# headphone-amp.net
KiCad netlist of a schematic drawn in EAGLE
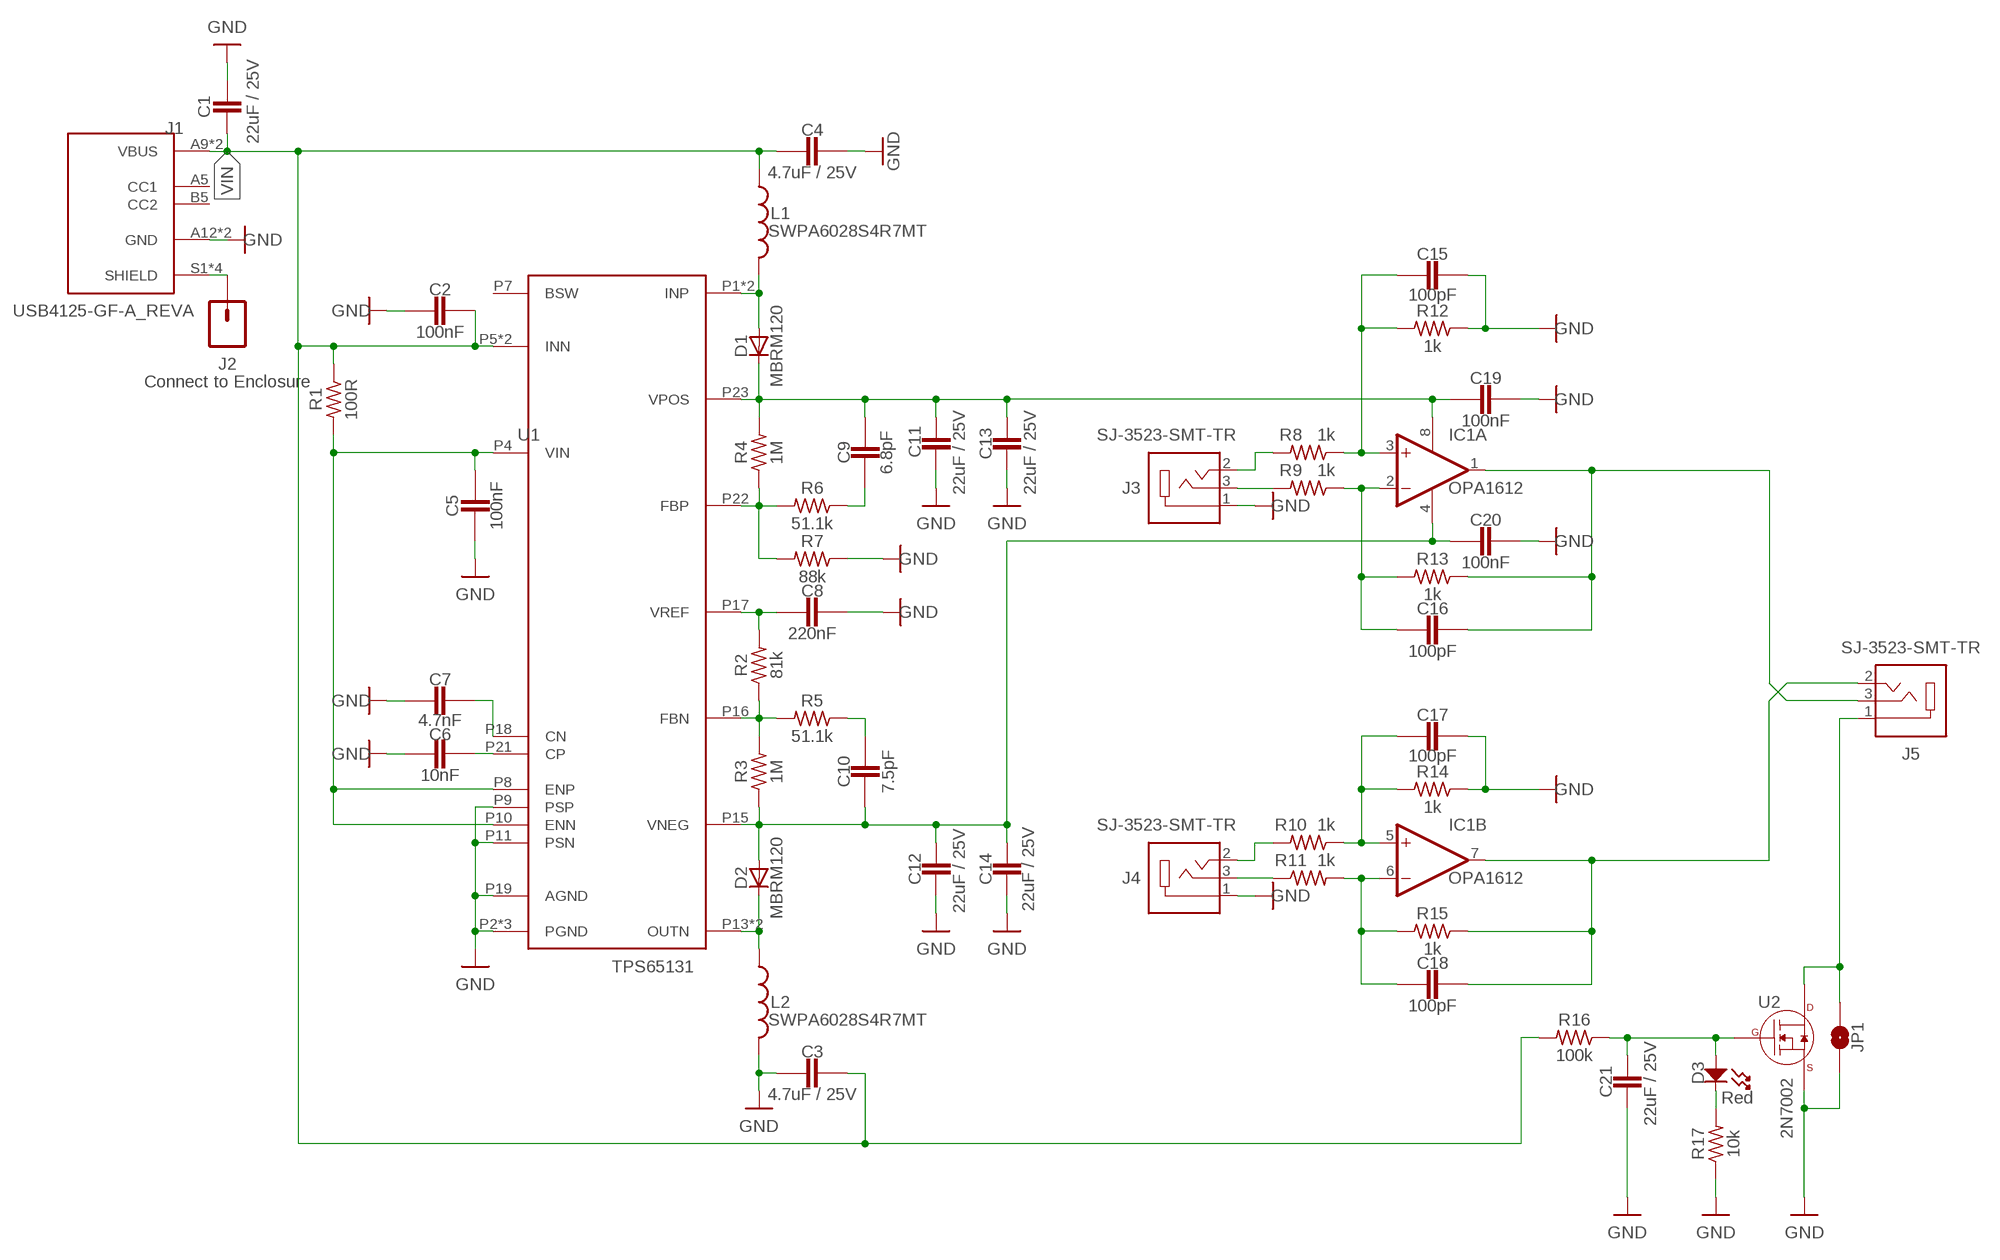
[diagram p0: schematic, sheet 1]

(export (version "E")
  (design (tool "Eeschema 10.0.6"))
  (components
    (comp (ref "C1")
      (value "22uF / 25V")
      (footprint "eagle-import:C0805")
      (libsource (lib "eagle-import") (part "C-EUC0805"))
    )
    (comp (ref "C2")
      (value "100nF")
      (footprint "eagle-import:C0402")
      (libsource (lib "eagle-import") (part "CAPACITOR-0402"))
    )
    (comp (ref "C3")
      (value "4.7uF / 25V")
      (footprint "eagle-import:C0402")
      (libsource (lib "eagle-import") (part "CAPACITOR-0402"))
    )
    (comp (ref "C4")
      (value "4.7uF / 25V")
      (footprint "eagle-import:C0402")
      (libsource (lib "eagle-import") (part "CAPACITOR-0402"))
    )
    (comp (ref "C5")
      (value "100nF")
      (footprint "eagle-import:C0402")
      (libsource (lib "eagle-import") (part "CAPACITOR-0402"))
    )
    (comp (ref "C6")
      (value "10nF")
      (footprint "eagle-import:C0402")
      (libsource (lib "eagle-import") (part "CAPACITOR-0402"))
    )
    (comp (ref "C7")
      (value "4.7nF")
      (footprint "eagle-import:C0402")
      (libsource (lib "eagle-import") (part "CAPACITOR-0402"))
    )
    (comp (ref "C8")
      (value "220nF")
      (footprint "eagle-import:C0402")
      (libsource (lib "eagle-import") (part "CAPACITOR-0402"))
    )
    (comp (ref "C9")
      (value "6.8pF")
      (footprint "eagle-import:C0402")
      (libsource (lib "eagle-import") (part "CAPACITOR-0402"))
    )
    (comp (ref "C10")
      (value "7.5pF")
      (footprint "eagle-import:C0402")
      (libsource (lib "eagle-import") (part "CAPACITOR-0402"))
    )
    (comp (ref "C11")
      (value "22uF / 25V")
      (footprint "eagle-import:C0805")
      (libsource (lib "eagle-import") (part "C-EUC0805"))
    )
    (comp (ref "C12")
      (value "22uF / 25V")
      (footprint "eagle-import:C0805")
      (libsource (lib "eagle-import") (part "C-EUC0805"))
    )
    (comp (ref "C13")
      (value "22uF / 25V")
      (footprint "eagle-import:C0805")
      (libsource (lib "eagle-import") (part "C-EUC0805"))
    )
    (comp (ref "C14")
      (value "22uF / 25V")
      (footprint "eagle-import:C0805")
      (libsource (lib "eagle-import") (part "C-EUC0805"))
    )
    (comp (ref "C15")
      (value "100pF")
      (footprint "eagle-import:C0402")
      (libsource (lib "eagle-import") (part "CAPACITOR-0402"))
    )
    (comp (ref "C16")
      (value "100pF")
      (footprint "eagle-import:C0402")
      (libsource (lib "eagle-import") (part "CAPACITOR-0402"))
    )
    (comp (ref "C17")
      (value "100pF")
      (footprint "eagle-import:C0402")
      (libsource (lib "eagle-import") (part "CAPACITOR-0402"))
    )
    (comp (ref "C18")
      (value "100pF")
      (footprint "eagle-import:C0402")
      (libsource (lib "eagle-import") (part "CAPACITOR-0402"))
    )
    (comp (ref "C19")
      (value "100nF")
      (footprint "eagle-import:C0402")
      (libsource (lib "eagle-import") (part "CAPACITOR-0402"))
    )
    (comp (ref "C20")
      (value "100nF")
      (footprint "eagle-import:C0402")
      (libsource (lib "eagle-import") (part "CAPACITOR-0402"))
    )
    (comp (ref "C21")
      (value "22uF / 25V")
      (footprint "eagle-import:C0805")
      (libsource (lib "eagle-import") (part "C-EUC0805"))
    )
    (comp (ref "D1")
      (value "MBRM120")
      (footprint "eagle-import:POWERMITE")
      (libsource (lib "eagle-import") (part "MBRM120"))
    )
    (comp (ref "D2")
      (value "MBRM120")
      (footprint "eagle-import:POWERMITE")
      (libsource (lib "eagle-import") (part "MBRM120"))
    )
    (comp (ref "D3")
      (value "Red")
      (footprint "eagle-import:LED0603")
      (fields (field (name "HOUSEPART") "NO"))
      (libsource (lib "eagle-import") (part "LED_SINGLE-0603"))
    )
    (comp (ref "IC1")
      (value "OPA1612")
      (footprint "eagle-import:SO08")
      (libsource (lib "eagle-import") (part "OPA2UA134"))
    )
    (comp (ref "J1")
      (value "USB4125-GF-A_REVA")
      (footprint "eagle-import:GCT_USB4125-GF-A_REVA")
      (fields (field (name "MF") "Global Connector Technology") (field (name "MP") "USB4125-GF-A"))
      (libsource (lib "eagle-import") (part "USB4125-GF-A_REVA"))
    )
    (comp (ref "J2")
      (value "CONN_01")
      (footprint "eagle-import:1X01")
      (libsource (lib "eagle-import") (part "CONN_01"))
    )
    (comp (ref "J3")
      (value "SJ-3523-SMT-TR")
      (footprint "eagle-import:CUI_SJ-3523-SMT-TR")
      (fields (field (name "MF") "CUI Devices"))
      (libsource (lib "eagle-import") (part "SJ-3523-SMT-TR"))
    )
    (comp (ref "J4")
      (value "SJ-3523-SMT-TR")
      (footprint "eagle-import:CUI_SJ-3523-SMT-TR")
      (fields (field (name "MF") "CUI Devices"))
      (libsource (lib "eagle-import") (part "SJ-3523-SMT-TR"))
    )
    (comp (ref "J5")
      (value "SJ-3523-SMT-TR")
      (footprint "eagle-import:CUI_SJ-3523-SMT-TR")
      (fields (field (name "MF") "CUI Devices"))
      (libsource (lib "eagle-import") (part "SJ-3523-SMT-TR"))
    )
    (comp (ref "JP1")
      (value "JUMPER-SMT_2_NO_SILK")
      (footprint "eagle-import:SMT-JUMPER_2_NO_SILK")
      (libsource (lib "eagle-import") (part "JUMPER-SMT_2_NO_SILK"))
    )
    (comp (ref "L1")
      (value "SWPA6028S4R7MT")
      (footprint "eagle-import:POWER-CHOKE_WE-TPC")
      (libsource (lib "eagle-import") (part "L-USWE-TPC"))
    )
    (comp (ref "L2")
      (value "SWPA6028S4R7MT")
      (footprint "eagle-import:POWER-CHOKE_WE-TPC")
      (libsource (lib "eagle-import") (part "L-USWE-TPC"))
    )
    (comp (ref "R1")
      (value "100R")
      (footprint "eagle-import:R0402")
      (libsource (lib "eagle-import") (part "R-US_R0402"))
    )
    (comp (ref "R2")
      (value "81k")
      (footprint "eagle-import:R0402")
      (libsource (lib "eagle-import") (part "R-US_R0402"))
    )
    (comp (ref "R3")
      (value "1M")
      (footprint "eagle-import:R0402")
      (libsource (lib "eagle-import") (part "R-US_R0402"))
    )
    (comp (ref "R4")
      (value "1M")
      (footprint "eagle-import:R0402")
      (libsource (lib "eagle-import") (part "R-US_R0402"))
    )
    (comp (ref "R5")
      (value "51.1k")
      (footprint "eagle-import:R0402")
      (libsource (lib "eagle-import") (part "R-US_R0402"))
    )
    (comp (ref "R6")
      (value "51.1k")
      (footprint "eagle-import:R0402")
      (libsource (lib "eagle-import") (part "R-US_R0402"))
    )
    (comp (ref "R7")
      (value "88k")
      (footprint "eagle-import:R0402")
      (libsource (lib "eagle-import") (part "R-US_R0402"))
    )
    (comp (ref "R8")
      (value "1k")
      (footprint "eagle-import:R0402")
      (libsource (lib "eagle-import") (part "R-US_R0402"))
    )
    (comp (ref "R9")
      (value "1k")
      (footprint "eagle-import:R0402")
      (libsource (lib "eagle-import") (part "R-US_R0402"))
    )
    (comp (ref "R10")
      (value "1k")
      (footprint "eagle-import:R0402")
      (libsource (lib "eagle-import") (part "R-US_R0402"))
    )
    (comp (ref "R11")
      (value "1k")
      (footprint "eagle-import:R0402")
      (libsource (lib "eagle-import") (part "R-US_R0402"))
    )
    (comp (ref "R12")
      (value "1k")
      (footprint "eagle-import:R0402")
      (libsource (lib "eagle-import") (part "R-US_R0402"))
    )
    (comp (ref "R13")
      (value "1k")
      (footprint "eagle-import:R0402")
      (libsource (lib "eagle-import") (part "R-US_R0402"))
    )
    (comp (ref "R14")
      (value "1k")
      (footprint "eagle-import:R0402")
      (libsource (lib "eagle-import") (part "R-US_R0402"))
    )
    (comp (ref "R15")
      (value "1k")
      (footprint "eagle-import:R0402")
      (libsource (lib "eagle-import") (part "R-US_R0402"))
    )
    (comp (ref "R16")
      (value "100k")
      (footprint "eagle-import:R0402")
      (libsource (lib "eagle-import") (part "R-US_R0402"))
    )
    (comp (ref "R17")
      (value "10k")
      (footprint "eagle-import:R0402")
      (libsource (lib "eagle-import") (part "R-US_R0402"))
    )
    (comp (ref "U1")
      (value "TPS65131")
      (footprint "eagle-import:QFN24-4X4-2")
      (libsource (lib "eagle-import") (part "TPS65131"))
    )
    (comp (ref "U2")
      (value "2N7002")
      (footprint "eagle-import:SOT-23-3")
      (fields (field (name "HOUSEPART") "NO"))
      (libsource (lib "eagle-import") (part "N-CHANNEL_FET_SOT-23-3"))
    )
  )
  (nets
    (net (code "1") (name "GND") (class "Default")
      (node (ref "C1") (pin "1") (pinfunction "1_1") (pintype "passive"))
      (node (ref "C11") (pin "2") (pinfunction "2_2") (pintype "passive"))
      (node (ref "C12") (pin "2") (pinfunction "2_2") (pintype "passive"))
      (node (ref "C13") (pin "2") (pinfunction "2_2") (pintype "passive"))
      (node (ref "C14") (pin "2") (pinfunction "2_2") (pintype "passive"))
      (node (ref "C15") (pin "1") (pinfunction "1_1") (pintype "passive"))
      (node (ref "C17") (pin "1") (pinfunction "1_1") (pintype "passive"))
      (node (ref "C19") (pin "2") (pinfunction "2_2") (pintype "passive"))
      (node (ref "C2") (pin "1") (pinfunction "1_1") (pintype "passive"))
      (node (ref "C20") (pin "2") (pinfunction "2_2") (pintype "passive"))
      (node (ref "C21") (pin "2") (pinfunction "2_2") (pintype "passive"))
      (node (ref "C3") (pin "2") (pinfunction "2_2") (pintype "passive"))
      (node (ref "C4") (pin "1") (pinfunction "1_1") (pintype "passive"))
      (node (ref "C5") (pin "2") (pinfunction "2_2") (pintype "passive"))
      (node (ref "C6") (pin "2") (pinfunction "2_2") (pintype "passive"))
      (node (ref "C7") (pin "2") (pinfunction "2_2") (pintype "passive"))
      (node (ref "C8") (pin "1") (pinfunction "1_1") (pintype "passive"))
      (node (ref "J1") (pin "A12") (pinfunction "GND_A12") (pintype "power_in"))
      (node (ref "J1") (pin "B12") (pinfunction "GND_B12") (pintype "power_in"))
      (node (ref "J3") (pin "1") (pinfunction "1_1") (pintype "passive"))
      (node (ref "J4") (pin "1") (pinfunction "1_1") (pintype "passive"))
      (node (ref "JP1") (pin "1") (pinfunction "1_1") (pintype "passive"))
      (node (ref "L2") (pin "2") (pinfunction "2_2") (pintype "passive"))
      (node (ref "R12") (pin "1") (pinfunction "1_1") (pintype "passive"))
      (node (ref "R14") (pin "1") (pinfunction "1_1") (pintype "passive"))
      (node (ref "R17") (pin "1") (pinfunction "1_1") (pintype "passive"))
      (node (ref "R7") (pin "1") (pinfunction "1_1") (pintype "passive"))
      (node (ref "U1") (pin "P11") (pinfunction "PSN_P11") (pintype "bidirectional"))
      (node (ref "U1") (pin "P19") (pinfunction "AGND_P19") (pintype "bidirectional"))
      (node (ref "U1") (pin "P2") (pinfunction "PGND_P2") (pintype "bidirectional"))
      (node (ref "U1") (pin "P3") (pinfunction "PGND_P3") (pintype "bidirectional"))
      (node (ref "U1") (pin "P9") (pinfunction "PSP_P9") (pintype "bidirectional"))
      (node (ref "U1") (pin "PAD") (pinfunction "PGND_PAD") (pintype "bidirectional"))
      (node (ref "U2") (pin "P$2") (pinfunction "SOURCE_P$2") (pintype "bidirectional"))
    )
    (net (code "2") (name "Net-(C9-Pad2)") (class "Default")
      (node (ref "C9") (pin "2") (pinfunction "2_2") (pintype "passive"))
      (node (ref "R6") (pin "1") (pinfunction "1_1") (pintype "passive"))
    )
    (net (code "3") (name "Net-(C10-Pad2)") (class "Default")
      (node (ref "C10") (pin "2") (pinfunction "2_2") (pintype "passive"))
      (node (ref "R5") (pin "1") (pinfunction "1_1") (pintype "passive"))
    )
    (net (code "4") (name "Net-(D1-A)") (class "Default")
      (node (ref "D1") (pin "P$2") (pinfunction "A_P$2") (pintype "passive"))
      (node (ref "L1") (pin "2") (pinfunction "2_2") (pintype "passive"))
      (node (ref "U1") (pin "P1") (pinfunction "INP_P1") (pintype "bidirectional"))
      (node (ref "U1") (pin "P24") (pinfunction "INP_P24") (pintype "bidirectional"))
    )
    (net (code "5") (name "Net-(D1-C)") (class "Default")
      (node (ref "C11") (pin "1") (pinfunction "1_1") (pintype "passive"))
      (node (ref "C13") (pin "1") (pinfunction "1_1") (pintype "passive"))
      (node (ref "C19") (pin "1") (pinfunction "1_1") (pintype "passive"))
      (node (ref "C9") (pin "1") (pinfunction "1_1") (pintype "passive"))
      (node (ref "D1") (pin "P$1") (pinfunction "C_P$1") (pintype "passive"))
      (node (ref "IC1") (pin "8") (pinfunction "V+_8") (pintype "power_in"))
      (node (ref "R4") (pin "2") (pinfunction "2_2") (pintype "passive"))
      (node (ref "U1") (pin "P23") (pinfunction "VPOS_P23") (pintype "bidirectional"))
    )
    (net (code "6") (name "Net-(D2-A)") (class "Default")
      (node (ref "C10") (pin "1") (pinfunction "1_1") (pintype "passive"))
      (node (ref "C12") (pin "1") (pinfunction "1_1") (pintype "passive"))
      (node (ref "C14") (pin "1") (pinfunction "1_1") (pintype "passive"))
      (node (ref "C20") (pin "1") (pinfunction "1_1") (pintype "passive"))
      (node (ref "D2") (pin "P$2") (pinfunction "A_P$2") (pintype "passive"))
      (node (ref "IC1") (pin "4") (pinfunction "V-_4") (pintype "power_in"))
      (node (ref "R3") (pin "1") (pinfunction "1_1") (pintype "passive"))
      (node (ref "U1") (pin "P15") (pinfunction "VNEG_P15") (pintype "bidirectional"))
    )
    (net (code "7") (name "Net-(D2-C)") (class "Default")
      (node (ref "D2") (pin "P$1") (pinfunction "C_P$1") (pintype "passive"))
      (node (ref "L2") (pin "1") (pinfunction "1_1") (pintype "passive"))
      (node (ref "U1") (pin "P13") (pinfunction "OUTN_P13") (pintype "bidirectional"))
      (node (ref "U1") (pin "P14") (pinfunction "OUTN_P14") (pintype "bidirectional"))
    )
    (net (code "8") (name "Net-(D3-PadCATHODE)") (class "Default")
      (node (ref "D3") (pin "CATHODE") (pinfunction "CATHODE_CATHODE") (pintype "power_in"))
      (node (ref "R17") (pin "2") (pinfunction "2_2") (pintype "passive"))
    )
    (net (code "9") (name "Net-(IC1A-+IN)") (class "Default")
      (node (ref "C15") (pin "2") (pinfunction "2_2") (pintype "passive"))
      (node (ref "IC1") (pin "3") (pinfunction "+IN_3") (pintype "input"))
      (node (ref "R12") (pin "2") (pinfunction "2_2") (pintype "passive"))
      (node (ref "R8") (pin "1") (pinfunction "1_1") (pintype "passive"))
    )
    (net (code "10") (name "Net-(IC1A--IN)") (class "Default")
      (node (ref "C16") (pin "2") (pinfunction "2_2") (pintype "passive"))
      (node (ref "IC1") (pin "2") (pinfunction "-IN_2") (pintype "input"))
      (node (ref "R13") (pin "2") (pinfunction "2_2") (pintype "passive"))
      (node (ref "R9") (pin "1") (pinfunction "1_1") (pintype "passive"))
    )
    (net (code "11") (name "Net-(IC1A-OUT)") (class "Default")
      (node (ref "C16") (pin "1") (pinfunction "1_1") (pintype "passive"))
      (node (ref "IC1") (pin "1") (pinfunction "OUT_1") (pintype "output"))
      (node (ref "J5") (pin "3") (pinfunction "3_3") (pintype "passive"))
      (node (ref "R13") (pin "1") (pinfunction "1_1") (pintype "passive"))
    )
    (net (code "12") (name "Net-(IC1B-+IN)") (class "Default")
      (node (ref "C17") (pin "2") (pinfunction "2_2") (pintype "passive"))
      (node (ref "IC1") (pin "5") (pinfunction "+IN_5") (pintype "input"))
      (node (ref "R10") (pin "1") (pinfunction "1_1") (pintype "passive"))
      (node (ref "R14") (pin "2") (pinfunction "2_2") (pintype "passive"))
    )
    (net (code "13") (name "Net-(IC1B--IN)") (class "Default")
      (node (ref "C18") (pin "2") (pinfunction "2_2") (pintype "passive"))
      (node (ref "IC1") (pin "6") (pinfunction "-IN_6") (pintype "input"))
      (node (ref "R11") (pin "2") (pinfunction "2_2") (pintype "passive"))
      (node (ref "R15") (pin "2") (pinfunction "2_2") (pintype "passive"))
    )
    (net (code "14") (name "Net-(IC1B-OUT)") (class "Default")
      (node (ref "C18") (pin "1") (pinfunction "1_1") (pintype "passive"))
      (node (ref "IC1") (pin "7") (pinfunction "OUT_7") (pintype "output"))
      (node (ref "J5") (pin "2") (pinfunction "2_2") (pintype "passive"))
      (node (ref "R15") (pin "1") (pinfunction "1_1") (pintype "passive"))
    )
    (net (code "15") (name "Net-(J1-SHIELD-PadS1)") (class "Default")
      (node (ref "J1") (pin "S1") (pinfunction "SHIELD_S1") (pintype "passive"))
      (node (ref "J1") (pin "S2") (pinfunction "SHIELD_S2") (pintype "passive"))
      (node (ref "J1") (pin "S3") (pinfunction "SHIELD_S3") (pintype "passive"))
      (node (ref "J1") (pin "S4") (pinfunction "SHIELD_S4") (pintype "passive"))
      (node (ref "J2") (pin "1") (pinfunction "1_1") (pintype "passive"))
    )
    (net (code "16") (name "Net-(J3-Pad2)") (class "Default")
      (node (ref "J3") (pin "2") (pinfunction "2_2") (pintype "passive"))
      (node (ref "R8") (pin "2") (pinfunction "2_2") (pintype "passive"))
    )
    (net (code "17") (name "Net-(J3-Pad3)") (class "Default")
      (node (ref "J3") (pin "3") (pinfunction "3_3") (pintype "passive"))
      (node (ref "R9") (pin "2") (pinfunction "2_2") (pintype "passive"))
    )
    (net (code "18") (name "Net-(J4-Pad2)") (class "Default")
      (node (ref "J4") (pin "2") (pinfunction "2_2") (pintype "passive"))
      (node (ref "R10") (pin "2") (pinfunction "2_2") (pintype "passive"))
    )
    (net (code "19") (name "Net-(J4-Pad3)") (class "Default")
      (node (ref "J4") (pin "3") (pinfunction "3_3") (pintype "passive"))
      (node (ref "R11") (pin "1") (pinfunction "1_1") (pintype "passive"))
    )
    (net (code "20") (name "Net-(U1-CN)") (class "Default")
      (node (ref "C7") (pin "1") (pinfunction "1_1") (pintype "passive"))
      (node (ref "U1") (pin "P18") (pinfunction "CN_P18") (pintype "bidirectional"))
    )
    (net (code "21") (name "Net-(U1-CP)") (class "Default")
      (node (ref "C6") (pin "1") (pinfunction "1_1") (pintype "passive"))
      (node (ref "U1") (pin "P21") (pinfunction "CP_P21") (pintype "bidirectional"))
    )
    (net (code "22") (name "Net-(U1-ENN)") (class "Default")
      (node (ref "C5") (pin "1") (pinfunction "1_1") (pintype "passive"))
      (node (ref "R1") (pin "2") (pinfunction "2_2") (pintype "passive"))
      (node (ref "U1") (pin "P10") (pinfunction "ENN_P10") (pintype "bidirectional"))
      (node (ref "U1") (pin "P4") (pinfunction "VIN_P4") (pintype "bidirectional"))
      (node (ref "U1") (pin "P8") (pinfunction "ENP_P8") (pintype "bidirectional"))
    )
    (net (code "23") (name "Net-(U1-FBN)") (class "Default")
      (node (ref "R2") (pin "1") (pinfunction "1_1") (pintype "passive"))
      (node (ref "R3") (pin "2") (pinfunction "2_2") (pintype "passive"))
      (node (ref "R5") (pin "2") (pinfunction "2_2") (pintype "passive"))
      (node (ref "U1") (pin "P16") (pinfunction "FBN_P16") (pintype "bidirectional"))
    )
    (net (code "24") (name "Net-(U1-FBP)") (class "Default")
      (node (ref "R4") (pin "1") (pinfunction "1_1") (pintype "passive"))
      (node (ref "R6") (pin "2") (pinfunction "2_2") (pintype "passive"))
      (node (ref "R7") (pin "2") (pinfunction "2_2") (pintype "passive"))
      (node (ref "U1") (pin "P22") (pinfunction "FBP_P22") (pintype "bidirectional"))
    )
    (net (code "25") (name "Net-(U1-VREF)") (class "Default")
      (node (ref "C8") (pin "2") (pinfunction "2_2") (pintype "passive"))
      (node (ref "R2") (pin "2") (pinfunction "2_2") (pintype "passive"))
      (node (ref "U1") (pin "P17") (pinfunction "VREF_P17") (pintype "bidirectional"))
    )
    (net (code "26") (name "Net-(U2-DRAIN)") (class "Default")
      (node (ref "J5") (pin "1") (pinfunction "1_1") (pintype "passive"))
      (node (ref "JP1") (pin "2") (pinfunction "2_2") (pintype "passive"))
      (node (ref "U2") (pin "P$3") (pinfunction "DRAIN_P$3") (pintype "bidirectional"))
    )
    (net (code "27") (name "Net-(U2-GATE)") (class "Default")
      (node (ref "C21") (pin "1") (pinfunction "1_1") (pintype "passive"))
      (node (ref "D3") (pin "ANODE") (pinfunction "ANODE_ANODE") (pintype "power_in"))
      (node (ref "R16") (pin "1") (pinfunction "1_1") (pintype "passive"))
      (node (ref "U2") (pin "P$1") (pinfunction "GATE_P$1") (pintype "bidirectional"))
    )
    (net (code "28") (name "VIN") (class "Default")
      (node (ref "C1") (pin "2") (pinfunction "2_2") (pintype "passive"))
      (node (ref "C2") (pin "2") (pinfunction "2_2") (pintype "passive"))
      (node (ref "C3") (pin "1") (pinfunction "1_1") (pintype "passive"))
      (node (ref "C4") (pin "2") (pinfunction "2_2") (pintype "passive"))
      (node (ref "J1") (pin "A9") (pinfunction "VBUS_A9") (pintype "power_in"))
      (node (ref "J1") (pin "B9") (pinfunction "VBUS_B9") (pintype "power_in"))
      (node (ref "L1") (pin "1") (pinfunction "1_1") (pintype "passive"))
      (node (ref "R1") (pin "1") (pinfunction "1_1") (pintype "passive"))
      (node (ref "R16") (pin "2") (pinfunction "2_2") (pintype "passive"))
      (node (ref "U1") (pin "P5") (pinfunction "INN_P5") (pintype "bidirectional"))
      (node (ref "U1") (pin "P6") (pinfunction "INN_P6") (pintype "bidirectional"))
    )
    (net (code "29") (name "unconnected-(J1-CC1-PadA5)") (class "Default")
      (node (ref "J1") (pin "A5") (pinfunction "CC1_A5") (pintype "bidirectional"))
    )
    (net (code "30") (name "unconnected-(J1-CC2-PadB5)") (class "Default")
      (node (ref "J1") (pin "B5") (pinfunction "CC2_B5") (pintype "bidirectional"))
    )
    (net (code "31") (name "unconnected-(U1-BSW-PadP7)") (class "Default")
      (node (ref "U1") (pin "P7") (pinfunction "BSW_P7") (pintype "bidirectional"))
    )
  )
)
